# PSU_1V2_LD1117A.net
KiCad netlist of a schematic drawn in Altium Designer
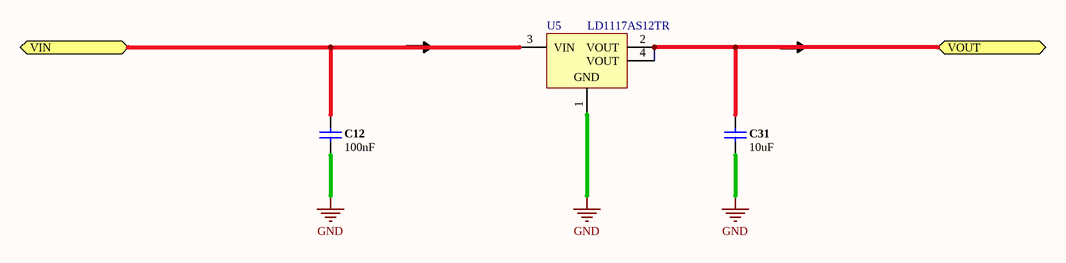
[diagram p0: PSU_1V2_LD1117A.SchDoc]

(export (version "E")
  (design (tool "Eeschema 10.0.6"))
  (components
    (comp (ref "C12")
      (value "100nF")
      (footprint "0805C-GENERIC")
      (description "Capacitor, Ceramic, 10% 10V 0603 X7R")
      (fields (field (name "CAPACITANCE") "100nF") (field (name "TOLERANCE") "10 %"))
      (libsource (lib "altium-import") (part "root_0_CAP-NP_"))
    )
    (comp (ref "C31")
      (value "10uF")
      (footprint "0805C-GENERIC")
      (description "Capacitor, Ceramic, 10% 10V 0805 X7R")
      (fields (field (name "CAPACITANCE") "10uF") (field (name "TOLERANCE") "10 %"))
      (libsource (lib "altium-import") (part "root_0_CAP-NP_"))
    )
    (comp (ref "U5")
      (value "LD1117AS12TR")
      (footprint "SOT-223_N")
      (description "1A, Low Drop Positive Voltage Regulator, 1.2V, 4-Pin SOT-223, Tape and Reel")
      (libsource (lib "STMicroelectronics Power Management Linear Regulator") (part "LD1117AS12TR"))
    )
  )
  (nets
    (net (code "1") (name "/VIN") (class "Default")
      (node (ref "C12") (pin "1") (pinfunction "1_1") (pintype "passive"))
      (node (ref "U5") (pin "3") (pinfunction "VIN_3") (pintype "power_in"))
    )
    (net (code "2") (name "/VOUT") (class "Default")
      (node (ref "C31") (pin "1") (pinfunction "1_1") (pintype "passive"))
      (node (ref "U5") (pin "2") (pinfunction "VOUT_2") (pintype "power_in"))
      (node (ref "U5") (pin "4") (pinfunction "VOUT_4") (pintype "power_in"))
    )
    (net (code "3") (name "GND") (class "Default")
      (node (ref "C12") (pin "2") (pinfunction "2_2") (pintype "passive"))
      (node (ref "C31") (pin "2") (pinfunction "2_2") (pintype "passive"))
      (node (ref "U5") (pin "1") (pinfunction "GND_1") (pintype "power_in"))
    )
  )
)
